# DACEM_Final_Bckup.net
KiCad netlist of a schematic drawn in EAGLE
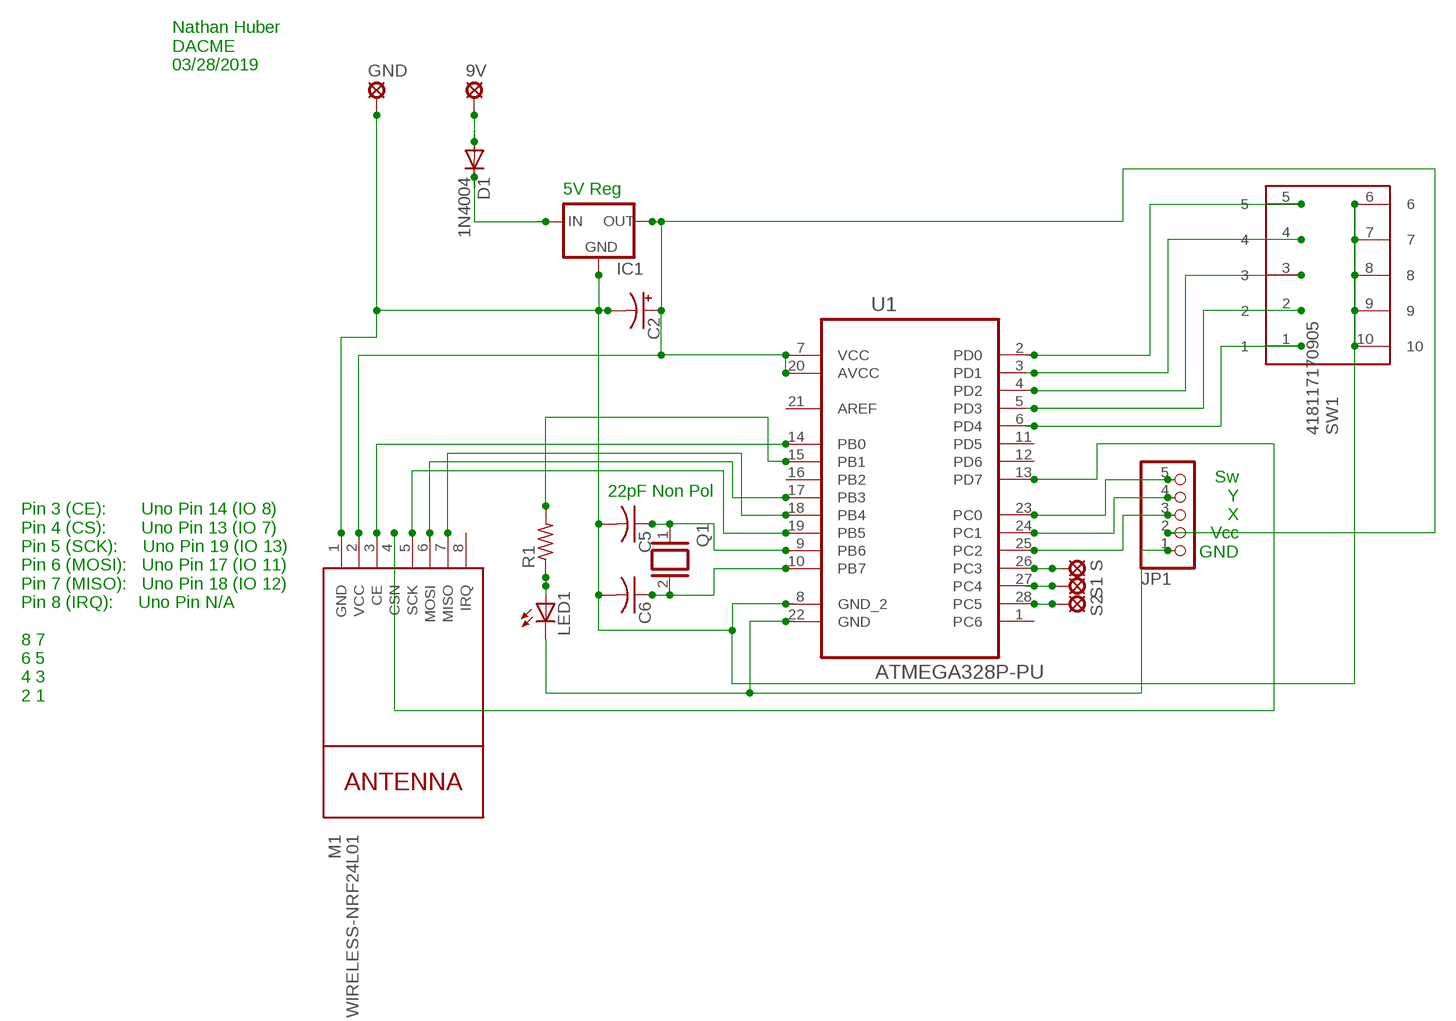
[diagram p0: schematic, sheet 1]

(export (version "E")
  (design (tool "Eeschema 10.0.6"))
  (components
    (comp (ref "9V")
      (value "LSP10")
      (footprint "eagle-import:LSP10")
      (libsource (lib "eagle-import") (part "LSP10"))
    )
    (comp (ref "C2")
      (value "CPOL-USE1.8-4")
      (footprint "eagle-import:E1,8-4")
      (libsource (lib "eagle-import") (part "CPOL-USE1.8-4"))
    )
    (comp (ref "C5")
      (value "C-US025-025X050")
      (footprint "eagle-import:C025-025X050")
      (libsource (lib "eagle-import") (part "C-US025-025X050"))
    )
    (comp (ref "C6")
      (value "C-US025-025X050")
      (footprint "eagle-import:C025-025X050")
      (libsource (lib "eagle-import") (part "C-US025-025X050"))
    )
    (comp (ref "D1")
      (value "1N4004")
      (footprint "eagle-import:DO41-10")
      (libsource (lib "eagle-import") (part "1N4004"))
    )
    (comp (ref "GND")
      (value "LSP10")
      (footprint "eagle-import:LSP10")
      (libsource (lib "eagle-import") (part "LSP10"))
    )
    (comp (ref "IC1")
      (value "78XXS")
      (footprint "eagle-import:78XXS")
      (libsource (lib "eagle-import") (part "78XXS"))
    )
    (comp (ref "JP1")
      (value "PINHD-1X5")
      (footprint "eagle-import:1X05")
      (libsource (lib "eagle-import") (part "PINHD-1X5"))
    )
    (comp (ref "LED1")
      (value "LED3MM")
      (footprint "eagle-import:LED3MM")
      (libsource (lib "eagle-import") (part "LED3MM"))
    )
    (comp (ref "M1")
      (value "WIRELESS-NRF24L01")
      (footprint "eagle-import:WIRELESS-NRF24L01")
      (libsource (lib "eagle-import") (part "WIRELESS-NRF24L01"))
    )
    (comp (ref "Q1")
      (value "XTAL")
      (footprint "eagle-import:Q")
      (libsource (lib "eagle-import") (part "XTAL"))
    )
    (comp (ref "R1")
      (value "R-US_0207/15")
      (footprint "eagle-import:0207_15")
      (libsource (lib "eagle-import") (part "R-US_0207/15"))
    )
    (comp (ref "S")
      (value "LSP10")
      (footprint "eagle-import:LSP10")
      (libsource (lib "eagle-import") (part "LSP10"))
    )
    (comp (ref "S1")
      (value "LSP10")
      (footprint "eagle-import:LSP10")
      (libsource (lib "eagle-import") (part "LSP10"))
    )
    (comp (ref "S2")
      (value "LSP10")
      (footprint "eagle-import:LSP10")
      (libsource (lib "eagle-import") (part "LSP10"))
    )
    (comp (ref "SW1")
      (value "418117170905")
      (footprint "eagle-import:418117170905")
      (libsource (lib "eagle-import") (part "418117170905"))
    )
    (comp (ref "U1")
      (value "ATMEGA328P-PU")
      (footprint "eagle-import:DIP254P762X457-28")
      (libsource (lib "eagle-import") (part "ATMEGA328P-PU"))
    )
  )
  (nets
    (net (code "1") (name "Net-(9V-PadMP)") (class "Default")
      (node (ref "9V") (pin "MP") (pinfunction "MP_MP") (pintype "passive"))
      (node (ref "D1") (pin "A") (pinfunction "A_A") (pintype "passive"))
    )
    (net (code "2") (name "Net-(D1-PadC)") (class "Default")
      (node (ref "D1") (pin "C") (pinfunction "C_C") (pintype "passive"))
      (node (ref "IC1") (pin "IN") (pinfunction "IN_IN") (pintype "input"))
    )
    (net (code "3") (name "Net-(LED1-C)") (class "Default")
      (node (ref "JP1") (pin "1") (pinfunction "1_1") (pintype "passive"))
      (node (ref "LED1") (pin "K") (pinfunction "C_K") (pintype "passive"))
      (node (ref "U1") (pin "22") (pinfunction "GND_22") (pintype "passive"))
    )
    (net (code "4") (name "Net-(LED1-PadA)") (class "Default")
      (node (ref "LED1") (pin "A") (pinfunction "A_A") (pintype "passive"))
      (node (ref "R1") (pin "1") (pinfunction "1_1") (pintype "passive"))
    )
    (net (code "5") (name "Net-(M1-CE)") (class "Default")
      (node (ref "M1") (pin "3") (pinfunction "CE_3") (pintype "bidirectional"))
      (node (ref "U1") (pin "14") (pinfunction "PB0_14") (pintype "bidirectional"))
    )
    (net (code "6") (name "Net-(M1-CSN)") (class "Default")
      (node (ref "M1") (pin "4") (pinfunction "CSN_4") (pintype "bidirectional"))
      (node (ref "U1") (pin "13") (pinfunction "PD7_13") (pintype "bidirectional"))
    )
    (net (code "7") (name "Net-(M1-GND)") (class "Default")
      (node (ref "C2") (pin "-") (pinfunction "-_-") (pintype "passive"))
      (node (ref "C5") (pin "2") (pinfunction "2_2") (pintype "passive"))
      (node (ref "C6") (pin "2") (pinfunction "2_2") (pintype "passive"))
      (node (ref "GND") (pin "MP") (pinfunction "MP_MP") (pintype "passive"))
      (node (ref "IC1") (pin "GND") (pinfunction "GND_GND") (pintype "input"))
      (node (ref "M1") (pin "1") (pinfunction "GND_1") (pintype "power_in"))
      (node (ref "SW1") (pin "10") (pinfunction "10_10") (pintype "bidirectional"))
      (node (ref "SW1") (pin "6") (pinfunction "6_6") (pintype "bidirectional"))
      (node (ref "SW1") (pin "7") (pinfunction "7_7") (pintype "bidirectional"))
      (node (ref "SW1") (pin "8") (pinfunction "8_8") (pintype "bidirectional"))
      (node (ref "SW1") (pin "9") (pinfunction "9_9") (pintype "bidirectional"))
      (node (ref "U1") (pin "8") (pinfunction "GND_2_8") (pintype "passive"))
    )
    (net (code "8") (name "Net-(M1-MISO)") (class "Default")
      (node (ref "M1") (pin "7") (pinfunction "MISO_7") (pintype "bidirectional"))
      (node (ref "U1") (pin "18") (pinfunction "PB4_18") (pintype "bidirectional"))
    )
    (net (code "9") (name "Net-(M1-MOSI)") (class "Default")
      (node (ref "M1") (pin "6") (pinfunction "MOSI_6") (pintype "bidirectional"))
      (node (ref "U1") (pin "17") (pinfunction "PB3_17") (pintype "bidirectional"))
    )
    (net (code "10") (name "Net-(M1-SCK)") (class "Default")
      (node (ref "M1") (pin "5") (pinfunction "SCK_5") (pintype "bidirectional"))
      (node (ref "U1") (pin "19") (pinfunction "PB5_19") (pintype "bidirectional"))
    )
    (net (code "11") (name "Net-(M1-VCC)") (class "Default")
      (node (ref "C2") (pin "+") (pinfunction "+_+") (pintype "passive"))
      (node (ref "IC1") (pin "OUT") (pinfunction "OUT_OUT") (pintype "passive"))
      (node (ref "JP1") (pin "2") (pinfunction "2_2") (pintype "passive"))
      (node (ref "M1") (pin "2") (pinfunction "VCC_2") (pintype "power_in"))
      (node (ref "U1") (pin "20") (pinfunction "AVCC_20") (pintype "power_in"))
      (node (ref "U1") (pin "7") (pinfunction "VCC_7") (pintype "power_in"))
    )
    (net (code "12") (name "Net-(U1-PB1)") (class "Default")
      (node (ref "R1") (pin "2") (pinfunction "2_2") (pintype "passive"))
      (node (ref "U1") (pin "15") (pinfunction "PB1_15") (pintype "bidirectional"))
    )
    (net (code "13") (name "Net-(U1-PB6)") (class "Default")
      (node (ref "C5") (pin "1") (pinfunction "1_1") (pintype "passive"))
      (node (ref "Q1") (pin "1") (pinfunction "1_1") (pintype "passive"))
      (node (ref "U1") (pin "9") (pinfunction "PB6_9") (pintype "bidirectional"))
    )
    (net (code "14") (name "Net-(U1-PB7)") (class "Default")
      (node (ref "C6") (pin "1") (pinfunction "1_1") (pintype "passive"))
      (node (ref "Q1") (pin "2") (pinfunction "2_2") (pintype "passive"))
      (node (ref "U1") (pin "10") (pinfunction "PB7_10") (pintype "bidirectional"))
    )
    (net (code "15") (name "Net-(U1-PC0)") (class "Default")
      (node (ref "JP1") (pin "5") (pinfunction "5_5") (pintype "passive"))
      (node (ref "U1") (pin "23") (pinfunction "PC0_23") (pintype "bidirectional"))
    )
    (net (code "16") (name "Net-(U1-PC1)") (class "Default")
      (node (ref "JP1") (pin "4") (pinfunction "4_4") (pintype "passive"))
      (node (ref "U1") (pin "24") (pinfunction "PC1_24") (pintype "bidirectional"))
    )
    (net (code "17") (name "Net-(U1-PC2)") (class "Default")
      (node (ref "JP1") (pin "3") (pinfunction "3_3") (pintype "passive"))
      (node (ref "U1") (pin "25") (pinfunction "PC2_25") (pintype "bidirectional"))
    )
    (net (code "18") (name "Net-(U1-PC3)") (class "Default")
      (node (ref "S") (pin "MP") (pinfunction "MP_MP") (pintype "passive"))
      (node (ref "U1") (pin "26") (pinfunction "PC3_26") (pintype "bidirectional"))
    )
    (net (code "19") (name "Net-(U1-PC4)") (class "Default")
      (node (ref "S1") (pin "MP") (pinfunction "MP_MP") (pintype "passive"))
      (node (ref "U1") (pin "27") (pinfunction "PC4_27") (pintype "bidirectional"))
    )
    (net (code "20") (name "Net-(U1-PC5)") (class "Default")
      (node (ref "S2") (pin "MP") (pinfunction "MP_MP") (pintype "passive"))
      (node (ref "U1") (pin "28") (pinfunction "PC5_28") (pintype "bidirectional"))
    )
    (net (code "21") (name "Net-(U1-PD0)") (class "Default")
      (node (ref "SW1") (pin "5") (pinfunction "5_5") (pintype "bidirectional"))
      (node (ref "U1") (pin "2") (pinfunction "PD0_2") (pintype "bidirectional"))
    )
    (net (code "22") (name "Net-(U1-PD1)") (class "Default")
      (node (ref "SW1") (pin "4") (pinfunction "4_4") (pintype "bidirectional"))
      (node (ref "U1") (pin "3") (pinfunction "PD1_3") (pintype "bidirectional"))
    )
    (net (code "23") (name "Net-(U1-PD2)") (class "Default")
      (node (ref "SW1") (pin "3") (pinfunction "3_3") (pintype "bidirectional"))
      (node (ref "U1") (pin "4") (pinfunction "PD2_4") (pintype "bidirectional"))
    )
    (net (code "24") (name "Net-(U1-PD3)") (class "Default")
      (node (ref "SW1") (pin "2") (pinfunction "2_2") (pintype "bidirectional"))
      (node (ref "U1") (pin "5") (pinfunction "PD3_5") (pintype "bidirectional"))
    )
    (net (code "25") (name "Net-(U1-PD4)") (class "Default")
      (node (ref "SW1") (pin "1") (pinfunction "1_1") (pintype "bidirectional"))
      (node (ref "U1") (pin "6") (pinfunction "PD4_6") (pintype "bidirectional"))
    )
    (net (code "26") (name "unconnected-(M1-IRQ-Pad8)") (class "Default")
      (node (ref "M1") (pin "8") (pinfunction "IRQ_8") (pintype "bidirectional"))
    )
    (net (code "27") (name "unconnected-(U1-AREF-Pad21)") (class "Default")
      (node (ref "U1") (pin "21") (pinfunction "AREF_21") (pintype "input"))
    )
    (net (code "28") (name "unconnected-(U1-PB2-Pad16)") (class "Default")
      (node (ref "U1") (pin "16") (pinfunction "PB2_16") (pintype "bidirectional"))
    )
    (net (code "29") (name "unconnected-(U1-PC6-Pad1)") (class "Default")
      (node (ref "U1") (pin "1") (pinfunction "PC6_1") (pintype "bidirectional"))
    )
    (net (code "30") (name "unconnected-(U1-PD5-Pad11)") (class "Default")
      (node (ref "U1") (pin "11") (pinfunction "PD5_11") (pintype "bidirectional"))
    )
    (net (code "31") (name "unconnected-(U1-PD6-Pad12)") (class "Default")
      (node (ref "U1") (pin "12") (pinfunction "PD6_12") (pintype "bidirectional"))
    )
  )
)
